# Sheet1.net
KiCad netlist of a schematic drawn in Altium Designer
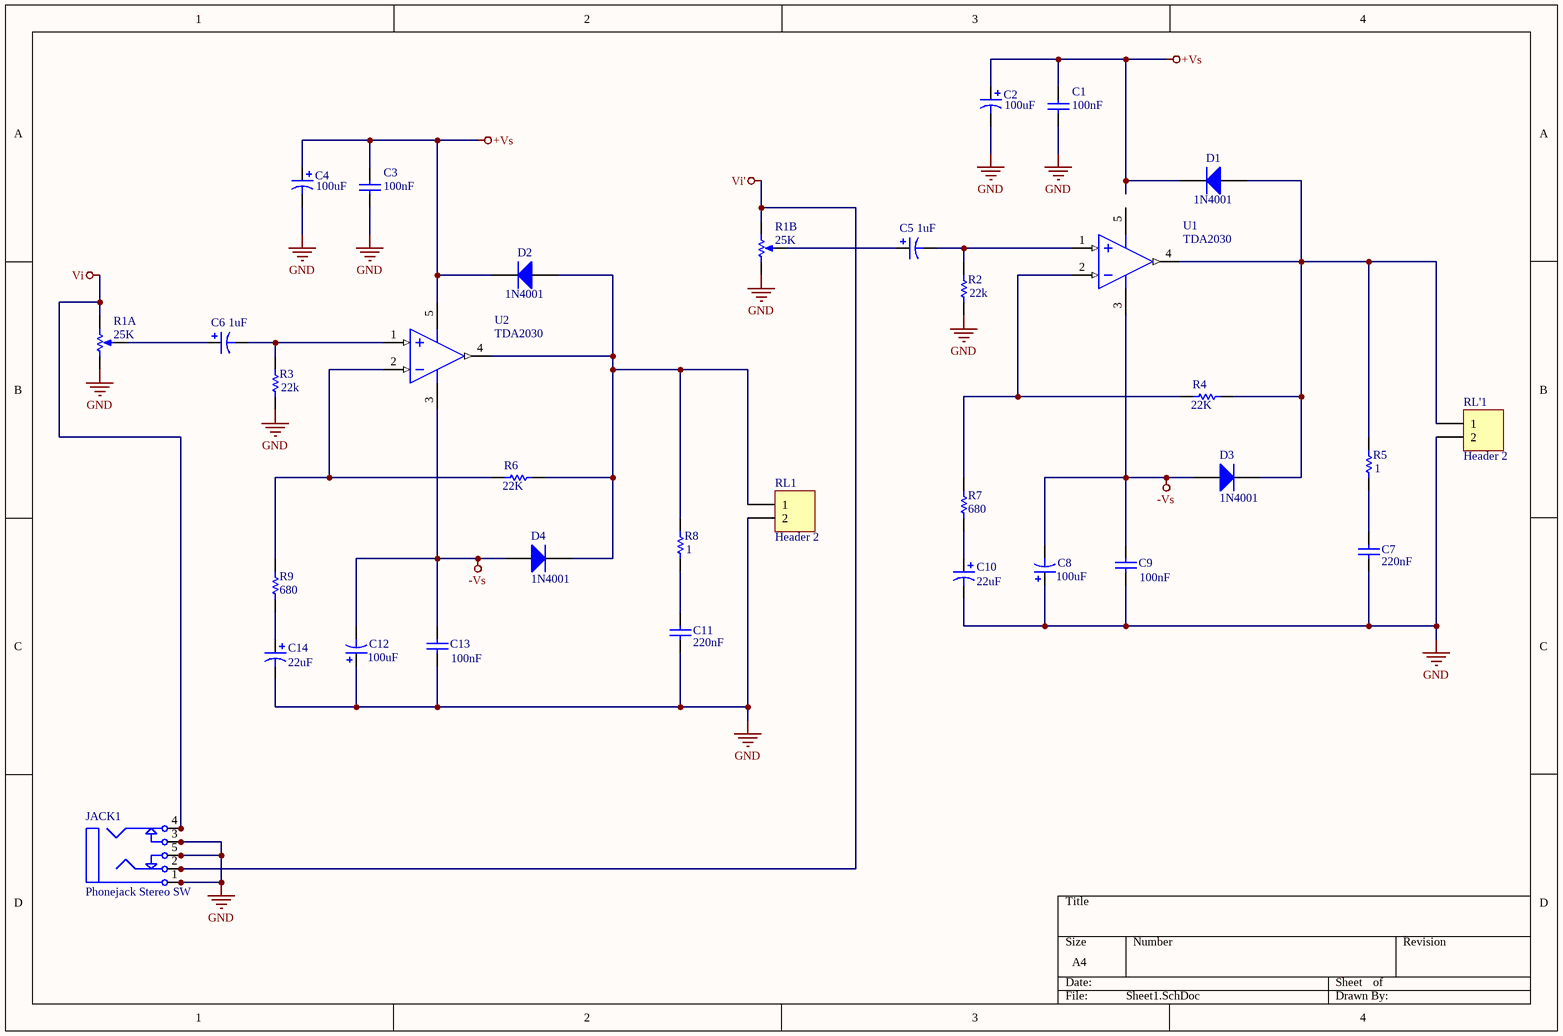
[diagram p0: Sheet1.SchDoc]

(export (version "E")
  (design (tool "Eeschema 10.0.6"))
  (components
    (comp (ref "C1")
      (value "100nF")
      (footprint "RAD-0.3")
      (description "Capacitor")
      (fields (field (name "Comment") "Cap") (field (name "PUBLISHER") "Altium Limited"))
      (libsource (lib "Miscellaneous Devices") (part "Cap"))
    )
    (comp (ref "C2")
      (value "100uF")
      (footprint "RB7.6-15")
      (description "Polarized Capacitor (Radial)")
      (fields (field (name "Comment") "Cap Pol1") (field (name "PUBLISHER") "Altium Limited"))
      (libsource (lib "Miscellaneous Devices") (part "Cap Pol1"))
    )
    (comp (ref "C3")
      (value "100nF")
      (footprint "RAD-0.3")
      (description "Capacitor")
      (fields (field (name "Comment") "Cap") (field (name "PUBLISHER") "Altium Limited"))
      (libsource (lib "Miscellaneous Devices") (part "Cap"))
    )
    (comp (ref "C4")
      (value "100uF")
      (footprint "RB7.6-15")
      (description "Polarized Capacitor (Radial)")
      (fields (field (name "Comment") "Cap Pol1") (field (name "PUBLISHER") "Altium Limited"))
      (libsource (lib "Miscellaneous Devices") (part "Cap Pol1"))
    )
    (comp (ref "C5")
      (value "1uF")
      (footprint "RB7.6-15")
      (description "Polarized Capacitor (Radial)")
      (fields (field (name "Comment") "Cap Pol1") (field (name "PUBLISHER") "Altium Limited"))
      (libsource (lib "Miscellaneous Devices") (part "Cap Pol1"))
    )
    (comp (ref "C6")
      (value "1uF")
      (footprint "RB7.6-15")
      (description "Polarized Capacitor (Radial)")
      (fields (field (name "Comment") "Cap Pol1") (field (name "PUBLISHER") "Altium Limited"))
      (libsource (lib "Miscellaneous Devices") (part "Cap Pol1"))
    )
    (comp (ref "C7")
      (value "220nF")
      (footprint "RAD-0.3")
      (description "Capacitor")
      (fields (field (name "Comment") "Cap") (field (name "PUBLISHER") "Altium Limited"))
      (libsource (lib "Miscellaneous Devices") (part "Cap"))
    )
    (comp (ref "C8")
      (value "100uF")
      (footprint "RB7.6-15")
      (description "Polarized Capacitor (Radial)")
      (fields (field (name "Comment") "Cap Pol1") (field (name "PUBLISHER") "Altium Limited"))
      (libsource (lib "Miscellaneous Devices") (part "Cap Pol1"))
    )
    (comp (ref "C9")
      (value "100nF")
      (footprint "RAD-0.3")
      (description "Capacitor")
      (fields (field (name "Comment") "Cap") (field (name "PUBLISHER") "Altium Limited"))
      (libsource (lib "Miscellaneous Devices") (part "Cap"))
    )
    (comp (ref "C10")
      (value "22uF")
      (footprint "RB7.6-15")
      (description "Polarized Capacitor (Radial)")
      (fields (field (name "Comment") "Cap Pol1") (field (name "PUBLISHER") "Altium Limited"))
      (libsource (lib "Miscellaneous Devices") (part "Cap Pol1"))
    )
    (comp (ref "C11")
      (value "220nF")
      (footprint "RAD-0.3")
      (description "Capacitor")
      (fields (field (name "Comment") "Cap") (field (name "PUBLISHER") "Altium Limited"))
      (libsource (lib "Miscellaneous Devices") (part "Cap"))
    )
    (comp (ref "C12")
      (value "100uF")
      (footprint "RB7.6-15")
      (description "Polarized Capacitor (Radial)")
      (fields (field (name "Comment") "Cap Pol1") (field (name "PUBLISHER") "Altium Limited"))
      (libsource (lib "Miscellaneous Devices") (part "Cap Pol1"))
    )
    (comp (ref "C13")
      (value "100nF")
      (footprint "RAD-0.3")
      (description "Capacitor")
      (fields (field (name "Comment") "Cap") (field (name "PUBLISHER") "Altium Limited"))
      (libsource (lib "Miscellaneous Devices") (part "Cap"))
    )
    (comp (ref "C14")
      (value "22uF")
      (footprint "RB7.6-15")
      (description "Polarized Capacitor (Radial)")
      (fields (field (name "Comment") "Cap Pol1") (field (name "PUBLISHER") "Altium Limited"))
      (libsource (lib "Miscellaneous Devices") (part "Cap Pol1"))
    )
    (comp (ref "D1")
      (value "1N4001")
      (footprint "DO-41")
      (description "1 Amp General Purpose Rectifier")
      (fields (field (name "PUBLISHER") "Altium Limited"))
      (libsource (lib "Miscellaneous Devices") (part "Diode 1N4001"))
    )
    (comp (ref "D2")
      (value "1N4001")
      (footprint "DO-41")
      (description "1 Amp General Purpose Rectifier")
      (fields (field (name "PUBLISHER") "Altium Limited"))
      (libsource (lib "Miscellaneous Devices") (part "Diode 1N4001"))
    )
    (comp (ref "D3")
      (value "1N4001")
      (footprint "DO-41")
      (description "1 Amp General Purpose Rectifier")
      (fields (field (name "PUBLISHER") "Altium Limited"))
      (libsource (lib "Miscellaneous Devices") (part "Diode 1N4001"))
    )
    (comp (ref "D4")
      (value "1N4001")
      (footprint "DO-41")
      (description "1 Amp General Purpose Rectifier")
      (fields (field (name "PUBLISHER") "Altium Limited"))
      (libsource (lib "Miscellaneous Devices") (part "Diode 1N4001"))
    )
    (comp (ref "JACK1")
      (value "Phonejack Stereo SW")
      (footprint "JACK FACHERO")
      (description "3-Conductor Jack with 2 break contacts (normals) and 2 auxiliary make contacts")
      (fields (field (name "PUBLISHER") "Altium Limited"))
      (libsource (lib "Miscellaneous Connectors") (part "Phonejack Stereo SW"))
    )
    (comp (ref "R1")
      (value "25K")
      (footprint "VR5")
      (description "Potentiometer")
      (fields (field (name "Comment") "RPot") (field (name "PUBLISHER") "Altium Limited"))
      (libsource (lib "Schlib1") (part "RPot"))
    )
    (comp (ref "R2")
      (value "22k")
      (footprint "AXIAL-0.3")
      (description "Resistor")
      (fields (field (name "Comment") "Res1") (field (name "PUBLISHER") "Altium Limited"))
      (libsource (lib "Miscellaneous Devices") (part "Res1"))
    )
    (comp (ref "R3")
      (value "22k")
      (footprint "AXIAL-0.3")
      (description "Resistor")
      (fields (field (name "Comment") "Res1") (field (name "PUBLISHER") "Altium Limited"))
      (libsource (lib "Miscellaneous Devices") (part "Res1"))
    )
    (comp (ref "R4")
      (value "22K")
      (footprint "AXIAL-0.3")
      (description "Resistor")
      (fields (field (name "Comment") "Res1") (field (name "PUBLISHER") "Altium Limited"))
      (libsource (lib "Miscellaneous Devices") (part "Res1"))
    )
    (comp (ref "R5")
      (value "1")
      (footprint "AXIAL-0.3")
      (description "Resistor")
      (fields (field (name "Comment") "Res1") (field (name "PUBLISHER") "Altium Limited"))
      (libsource (lib "Miscellaneous Devices") (part "Res1"))
    )
    (comp (ref "R6")
      (value "22K")
      (footprint "AXIAL-0.3")
      (description "Resistor")
      (fields (field (name "Comment") "Res1") (field (name "PUBLISHER") "Altium Limited"))
      (libsource (lib "Miscellaneous Devices") (part "Res1"))
    )
    (comp (ref "R7")
      (value "680")
      (footprint "AXIAL-0.3")
      (description "Resistor")
      (fields (field (name "Comment") "Res1") (field (name "PUBLISHER") "Altium Limited"))
      (libsource (lib "Miscellaneous Devices") (part "Res1"))
    )
    (comp (ref "R8")
      (value "1")
      (footprint "AXIAL-0.3")
      (description "Resistor")
      (fields (field (name "Comment") "Res1") (field (name "PUBLISHER") "Altium Limited"))
      (libsource (lib "Miscellaneous Devices") (part "Res1"))
    )
    (comp (ref "R9")
      (value "680")
      (footprint "AXIAL-0.3")
      (description "Resistor")
      (fields (field (name "Comment") "Res1") (field (name "PUBLISHER") "Altium Limited"))
      (libsource (lib "Miscellaneous Devices") (part "Res1"))
    )
    (comp (ref "RL'1")
      (value "Header 2")
      (footprint "HDR1X2")
      (description "Header, 2-Pin")
      (fields (field (name "PUBLISHER") "Altium Limited"))
      (libsource (lib "Miscellaneous Connectors") (part "Header 2"))
    )
    (comp (ref "RL1")
      (value "Header 2")
      (footprint "HDR1X2")
      (description "Header, 2-Pin")
      (fields (field (name "PUBLISHER") "Altium Limited"))
      (libsource (lib "Miscellaneous Connectors") (part "Header 2"))
    )
    (comp (ref "U1")
      (value "TDA2030")
      (footprint "PentawattV")
      (description "Dual Operational Amplifier")
      (fields (field (name "PUBLISHER") "Altium Limited"))
      (libsource (lib "Schlib1") (part "TDA2030"))
    )
    (comp (ref "U2")
      (value "TDA2030")
      (footprint "PentawattV")
      (description "Dual Operational Amplifier")
      (fields (field (name "PUBLISHER") "Altium Limited"))
      (libsource (lib "Schlib1") (part "TDA2030"))
    )
  )
  (nets
    (net (code "1") (name "+Vs") (class "Default")
      (node (ref "C1") (pin "2") (pinfunction "2_2") (pintype "passive"))
      (node (ref "C2") (pin "1") (pinfunction "1_1") (pintype "passive"))
      (node (ref "C3") (pin "2") (pinfunction "2_2") (pintype "passive"))
      (node (ref "C4") (pin "1") (pinfunction "1_1") (pintype "passive"))
      (node (ref "D1") (pin "2") (pinfunction "K_2") (pintype "passive"))
      (node (ref "D2") (pin "2") (pinfunction "K_2") (pintype "passive"))
      (node (ref "U2") (pin "5") (pinfunction "V+_5") (pintype "power_in"))
    )
    (net (code "2") (name "-Vs") (class "Default")
      (node (ref "C12") (pin "2") (pinfunction "2_2") (pintype "passive"))
      (node (ref "C13") (pin "2") (pinfunction "2_2") (pintype "passive"))
      (node (ref "C8") (pin "2") (pinfunction "2_2") (pintype "passive"))
      (node (ref "C9") (pin "2") (pinfunction "2_2") (pintype "passive"))
      (node (ref "D3") (pin "1") (pinfunction "A_1") (pintype "passive"))
      (node (ref "D4") (pin "1") (pinfunction "A_1") (pintype "passive"))
      (node (ref "U1") (pin "3") (pinfunction "V-_3") (pintype "power_in"))
      (node (ref "U2") (pin "3") (pinfunction "V-_3") (pintype "power_in"))
    )
    (net (code "3") (name "GND") (class "Default")
      (node (ref "C1") (pin "1") (pinfunction "1_1") (pintype "passive"))
      (node (ref "C10") (pin "2") (pinfunction "2_2") (pintype "passive"))
      (node (ref "C11") (pin "1") (pinfunction "1_1") (pintype "passive"))
      (node (ref "C12") (pin "1") (pinfunction "1_1") (pintype "passive"))
      (node (ref "C13") (pin "1") (pinfunction "1_1") (pintype "passive"))
      (node (ref "C14") (pin "2") (pinfunction "2_2") (pintype "passive"))
      (node (ref "C2") (pin "2") (pinfunction "2_2") (pintype "passive"))
      (node (ref "C3") (pin "1") (pinfunction "1_1") (pintype "passive"))
      (node (ref "C4") (pin "2") (pinfunction "2_2") (pintype "passive"))
      (node (ref "C7") (pin "1") (pinfunction "1_1") (pintype "passive"))
      (node (ref "C8") (pin "1") (pinfunction "1_1") (pintype "passive"))
      (node (ref "C9") (pin "1") (pinfunction "1_1") (pintype "passive"))
      (node (ref "JACK1") (pin "1") (pinfunction "1_1") (pintype "passive"))
      (node (ref "JACK1") (pin "1A") (pinfunction "1A_1A") (pintype "passive"))
      (node (ref "JACK1") (pin "1B") (pinfunction "1B_1B") (pintype "passive"))
      (node (ref "JACK1") (pin "3") (pinfunction "3_3") (pintype "passive"))
      (node (ref "JACK1") (pin "3A") (pinfunction "3A_3A") (pintype "passive"))
      (node (ref "JACK1") (pin "3B") (pinfunction "3B_3B") (pintype "passive"))
      (node (ref "JACK1") (pin "5") (pinfunction "5_5") (pintype "passive"))
      (node (ref "JACK1") (pin "5A") (pinfunction "5A_5A") (pintype "passive"))
      (node (ref "JACK1") (pin "5B") (pinfunction "5B_5B") (pintype "passive"))
      (node (ref "R1") (pin "1") (pinfunction "TOP_1") (pintype "passive"))
      (node (ref "R2") (pin "1") (pinfunction "1_1") (pintype "passive"))
      (node (ref "R3") (pin "1") (pinfunction "1_1") (pintype "passive"))
      (node (ref "RL'1") (pin "2") (pinfunction "2_2") (pintype "passive"))
      (node (ref "RL1") (pin "2") (pinfunction "2_2") (pintype "passive"))
    )
    (net (code "4") (name "Net-(C7-Pad2)") (class "Default")
      (node (ref "C7") (pin "2") (pinfunction "2_2") (pintype "passive"))
      (node (ref "R5") (pin "1") (pinfunction "1_1") (pintype "passive"))
    )
    (net (code "5") (name "Net-(C10-Pad1)") (class "Default")
      (node (ref "C10") (pin "1") (pinfunction "1_1") (pintype "passive"))
      (node (ref "R7") (pin "1") (pinfunction "1_1") (pintype "passive"))
    )
    (net (code "6") (name "Net-(C11-Pad2)") (class "Default")
      (node (ref "C11") (pin "2") (pinfunction "2_2") (pintype "passive"))
      (node (ref "R8") (pin "1") (pinfunction "1_1") (pintype "passive"))
    )
    (net (code "7") (name "Net-(C14-Pad1)") (class "Default")
      (node (ref "C14") (pin "1") (pinfunction "1_1") (pintype "passive"))
      (node (ref "R9") (pin "1") (pinfunction "1_1") (pintype "passive"))
    )
    (net (code "8") (name "Net-(D1-A)") (class "Default")
      (node (ref "D1") (pin "1") (pinfunction "A_1") (pintype "passive"))
      (node (ref "D3") (pin "2") (pinfunction "K_2") (pintype "passive"))
      (node (ref "R4") (pin "1") (pinfunction "1_1") (pintype "passive"))
      (node (ref "R5") (pin "2") (pinfunction "2_2") (pintype "passive"))
      (node (ref "RL'1") (pin "1") (pinfunction "1_1") (pintype "passive"))
      (node (ref "U1") (pin "4") (pinfunction "OUT_4") (pintype "output"))
    )
    (net (code "9") (name "Net-(D2-A)") (class "Default")
      (node (ref "D2") (pin "1") (pinfunction "A_1") (pintype "passive"))
      (node (ref "D4") (pin "2") (pinfunction "K_2") (pintype "passive"))
      (node (ref "R6") (pin "1") (pinfunction "1_1") (pintype "passive"))
      (node (ref "R8") (pin "2") (pinfunction "2_2") (pintype "passive"))
      (node (ref "RL1") (pin "1") (pinfunction "1_1") (pintype "passive"))
      (node (ref "U2") (pin "4") (pinfunction "OUT_4") (pintype "output"))
    )
    (net (code "10") (name "Net-(R1A-TAP)") (class "Default")
      (node (ref "C6") (pin "1") (pinfunction "1_1") (pintype "passive"))
      (node (ref "R1") (pin "3") (pinfunction "TAP_3") (pintype "passive"))
    )
    (net (code "11") (name "Net-(R1B-TAP)") (class "Default")
      (node (ref "C5") (pin "1") (pinfunction "1_1") (pintype "passive"))
      (node (ref "R1") (pin "3") (pinfunction "TAP_3") (pintype "passive"))
    )
    (net (code "12") (name "Net-(U1-IN+)") (class "Default")
      (node (ref "C5") (pin "2") (pinfunction "2_2") (pintype "passive"))
      (node (ref "R2") (pin "2") (pinfunction "2_2") (pintype "passive"))
      (node (ref "U1") (pin "1") (pinfunction "IN+_1") (pintype "input"))
    )
    (net (code "13") (name "Net-(U1-IN-)") (class "Default")
      (node (ref "R4") (pin "2") (pinfunction "2_2") (pintype "passive"))
      (node (ref "R7") (pin "2") (pinfunction "2_2") (pintype "passive"))
      (node (ref "U1") (pin "2") (pinfunction "IN-_2") (pintype "input"))
    )
    (net (code "14") (name "Net-(U2-IN+)") (class "Default")
      (node (ref "C6") (pin "2") (pinfunction "2_2") (pintype "passive"))
      (node (ref "R3") (pin "2") (pinfunction "2_2") (pintype "passive"))
      (node (ref "U2") (pin "1") (pinfunction "IN+_1") (pintype "input"))
    )
    (net (code "15") (name "Net-(U2-IN-)") (class "Default")
      (node (ref "R6") (pin "2") (pinfunction "2_2") (pintype "passive"))
      (node (ref "R9") (pin "2") (pinfunction "2_2") (pintype "passive"))
      (node (ref "U2") (pin "2") (pinfunction "IN-_2") (pintype "input"))
    )
    (net (code "16") (name "Vi") (class "Default")
      (node (ref "JACK1") (pin "4") (pinfunction "4_4") (pintype "passive"))
      (node (ref "JACK1") (pin "4A") (pinfunction "4A_4A") (pintype "passive"))
      (node (ref "JACK1") (pin "4B") (pinfunction "4B_4B") (pintype "passive"))
      (node (ref "R1") (pin "2") (pinfunction "BOT_2") (pintype "passive"))
    )
    (net (code "17") (name "Vi'") (class "Default")
      (node (ref "JACK1") (pin "2") (pinfunction "2_2") (pintype "passive"))
      (node (ref "JACK1") (pin "2A") (pinfunction "2A_2A") (pintype "passive"))
      (node (ref "JACK1") (pin "2B") (pinfunction "2B_2B") (pintype "passive"))
      (node (ref "R1") (pin "2") (pinfunction "BOT_2") (pintype "passive"))
    )
    (net (code "18") (name "unconnected-(U1-V+-Pad5)") (class "Default")
      (node (ref "U1") (pin "5") (pinfunction "V+_5") (pintype "power_in"))
    )
  )
)
